# 03__Actuators_Driver_Sheet.net
KiCad netlist of a schematic drawn in Altium Designer
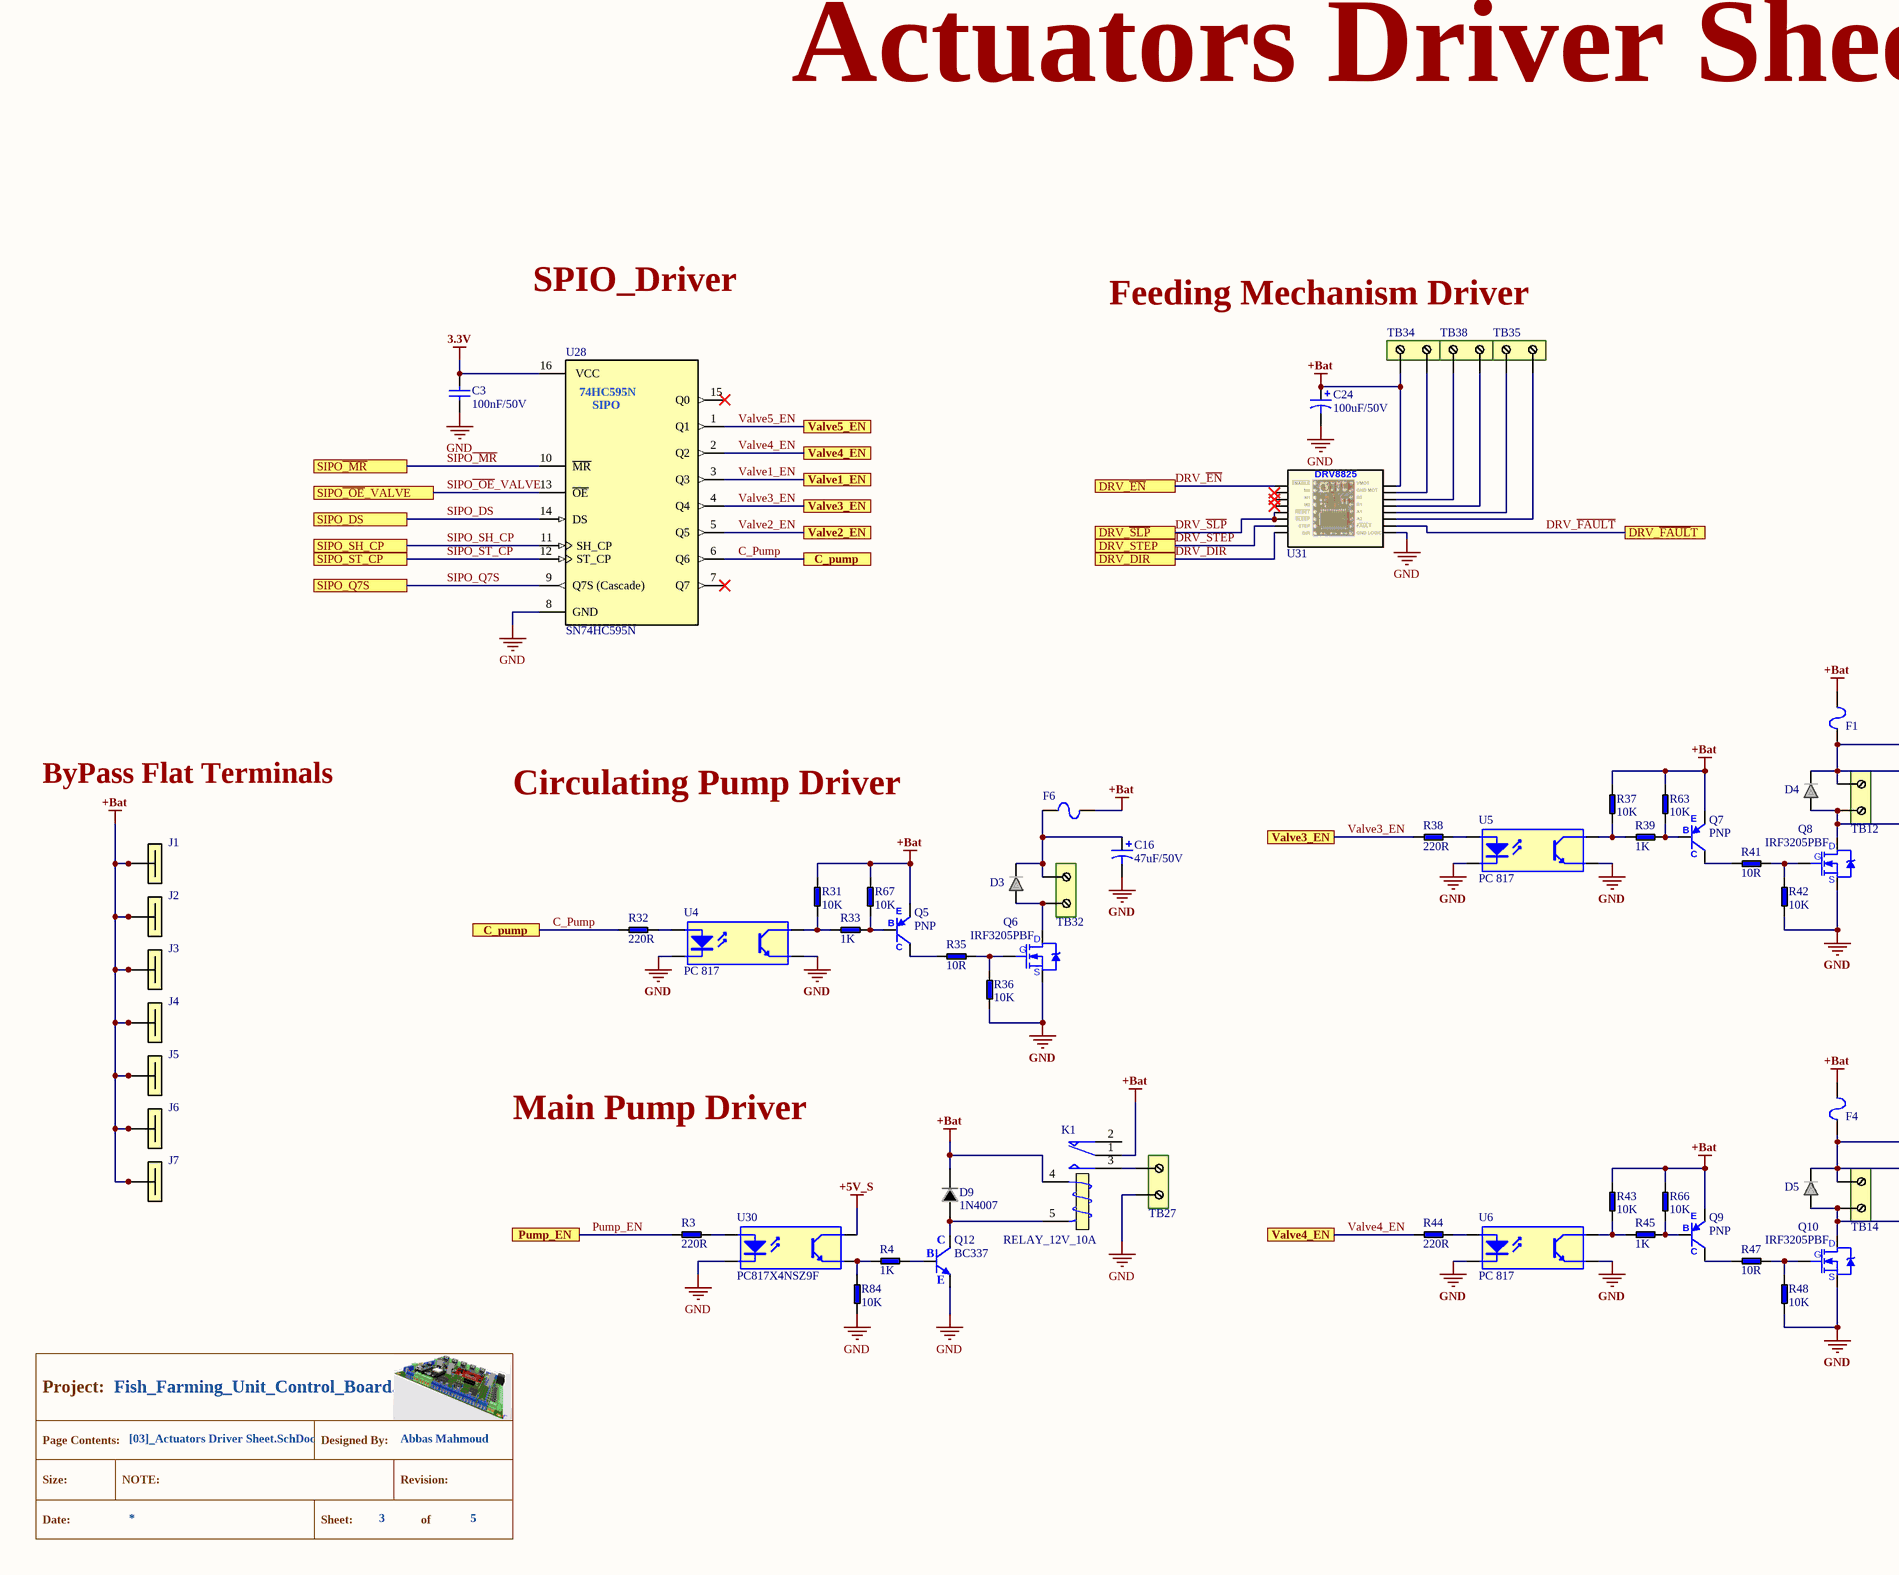
[diagram p0: [03]_Actuators Driver Sheet.SchDoc, left]
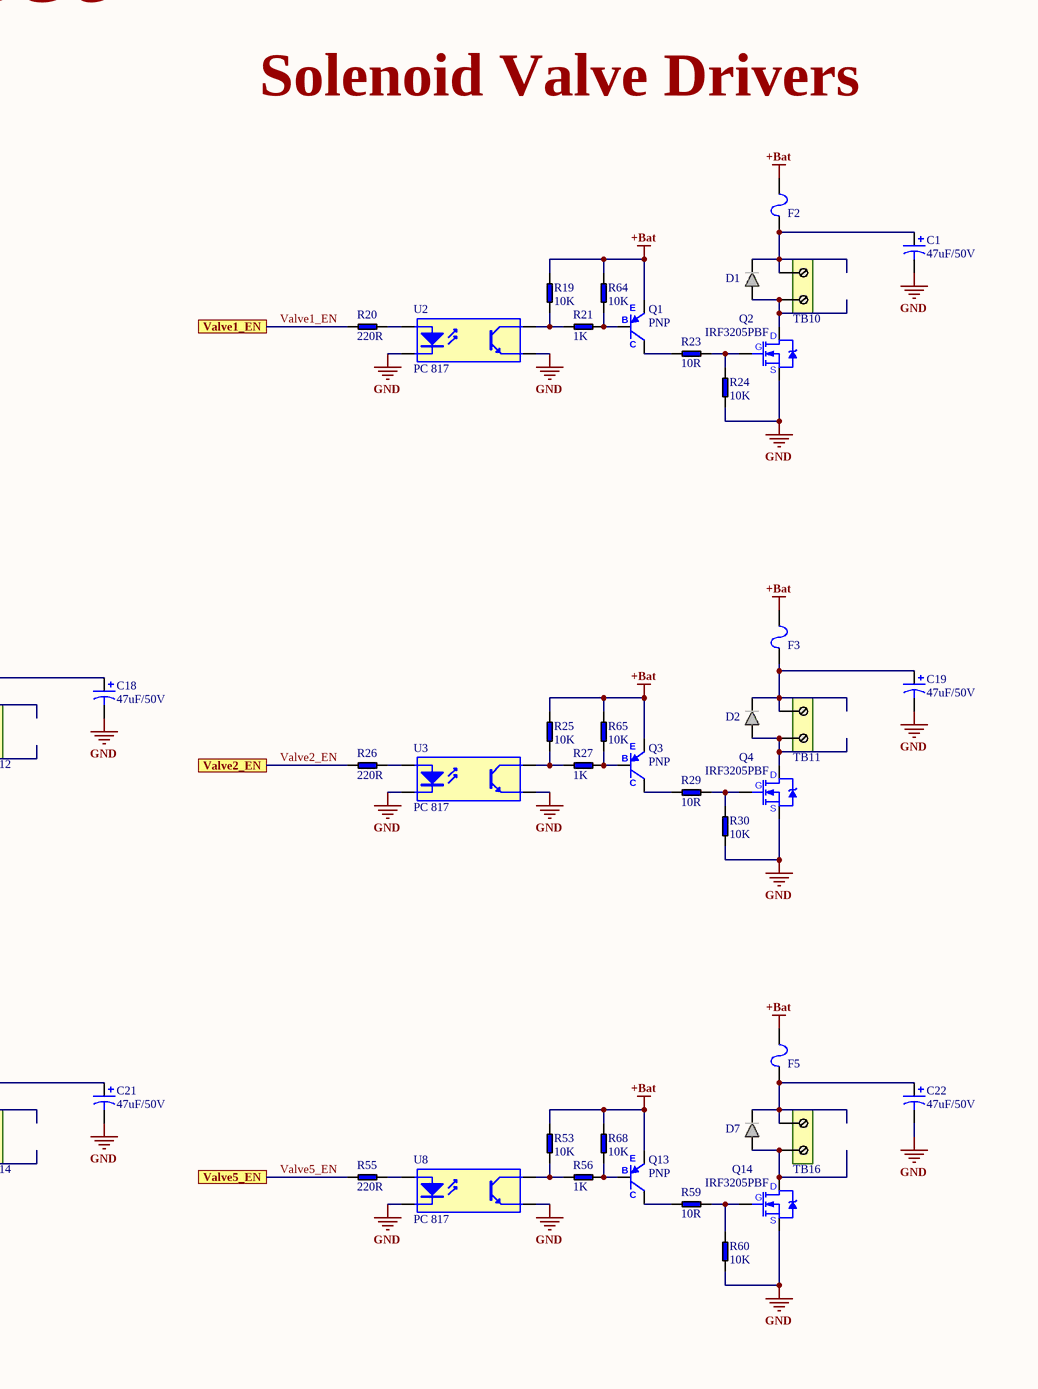
[diagram p1: [03]_Actuators Driver Sheet.SchDoc, right]

(export (version "E")
  (design (tool "Eeschema 10.0.6"))
  (components
    (comp (ref "C1")
      (value "47uF/50V")
      (footprint "ECAP - THT - 6.3X11X2.5MM")
      (description "47uF ±20% 50V 6.3x11 1000Hrs @ 105℃ Radial,6.3x11mm Aluminum Electrolytic Capacitors - Leaded RoHS")
      (libsource (lib "Altium_Abbas_V3") (part "ECAP - 47uF - 50V"))
    )
    (comp (ref "C3")
      (value "100nF/50V")
      (footprint "CCAP - PACKAGE - THT ,P = 2.54 MM")
      (description "100nF -20%~+80% 50V Through Hole,P=2.54mm Ceramic Disc Capacitors RoHS")
      (libsource (lib "Altium_Abbas_V3") (part "CCAP - 100nF - 50V - THT - P = 2.54"))
    )
    (comp (ref "C16")
      (value "47uF/50V")
      (footprint "ECAP - THT - 6.3X11X2.5MM")
      (description "47uF ±20% 50V 6.3x11 1000Hrs @ 105℃ Radial,6.3x11mm Aluminum Electrolytic Capacitors - Leaded RoHS")
      (libsource (lib "Altium_Abbas_V3") (part "ECAP - 47uF - 50V"))
    )
    (comp (ref "C18")
      (value "47uF/50V")
      (footprint "ECAP - THT - 6.3X11X2.5MM")
      (description "47uF ±20% 50V 6.3x11 1000Hrs @ 105℃ Radial,6.3x11mm Aluminum Electrolytic Capacitors - Leaded RoHS")
      (libsource (lib "Altium_Abbas_V3") (part "ECAP - 47uF - 50V"))
    )
    (comp (ref "C19")
      (value "47uF/50V")
      (footprint "ECAP - THT - 6.3X11X2.5MM")
      (description "47uF ±20% 50V 6.3x11 1000Hrs @ 105℃ Radial,6.3x11mm Aluminum Electrolytic Capacitors - Leaded RoHS")
      (libsource (lib "Altium_Abbas_V3") (part "ECAP - 47uF - 50V"))
    )
    (comp (ref "C21")
      (value "47uF/50V")
      (footprint "ECAP - THT - 6.3X11X2.5MM")
      (description "47uF ±20% 50V 6.3x11 1000Hrs @ 105℃ Radial,6.3x11mm Aluminum Electrolytic Capacitors - Leaded RoHS")
      (libsource (lib "Altium_Abbas_V3") (part "ECAP - 47uF - 50V"))
    )
    (comp (ref "C22")
      (value "47uF/50V")
      (footprint "ECAP - THT - 6.3X11X2.5MM")
      (description "47uF ±20% 50V 6.3x11 1000Hrs @ 105℃ Radial,6.3x11mm Aluminum Electrolytic Capacitors - Leaded RoHS")
      (libsource (lib "Altium_Abbas_V3") (part "ECAP - 47uF - 50V"))
    )
    (comp (ref "C24")
      (value "100uF/50V")
      (footprint "ECAP - THT - 8X12X3.5MM")
      (description "100uF ±20% 50V 8x12 1000Hrs @ 105℃ Radial,8x12mm Aluminum Electrolytic Capacitors - Leaded RoHS")
      (libsource (lib "Altium_Abbas_V3") (part "ECAP - 100uF - 50V"))
    )
    (comp (ref "D1")
      (value "DIODE")
      (footprint "DIODE-1n400X_0.3")
      (libsource (lib "Altium_Abbas") (part "DIODE"))
    )
    (comp (ref "D2")
      (value "DIODE")
      (footprint "DIODE-1n400X_0.3")
      (libsource (lib "Altium_Abbas") (part "DIODE"))
    )
    (comp (ref "D3")
      (value "DIODE")
      (footprint "DIODE-1n400X_0.3")
      (libsource (lib "Altium_Abbas") (part "DIODE"))
    )
    (comp (ref "D4")
      (value "DIODE")
      (footprint "DIODE-1n400X_0.3")
      (libsource (lib "Altium_Abbas") (part "DIODE"))
    )
    (comp (ref "D5")
      (value "DIODE")
      (footprint "DIODE-1n400X_0.3")
      (libsource (lib "Altium_Abbas") (part "DIODE"))
    )
    (comp (ref "D7")
      (value "DIODE")
      (footprint "DIODE-1n400X_0.3")
      (libsource (lib "Altium_Abbas") (part "DIODE"))
    )
    (comp (ref "D9")
      (value "1N4007")
      (footprint "DIODE - THT - 7.62P - PACKAGE - DO-41")
      (description "1kV 1A 1V @ 1A DO-41 Diodes - General Purpose RoHS")
      (libsource (lib "Altium_Abbas_V3") (part "Diode - 1N4007 - THT"))
    )
    (comp (ref "F1")
      (value "FUSES&HOLDERS")
      (footprint "FUSE-BLX-A HOLDER")
      (libsource (lib "Altium_Abbas_V3") (part "FUSES&HOLDERS"))
    )
    (comp (ref "F2")
      (value "FUSES&HOLDERS")
      (footprint "FUSE-BLX-A HOLDER")
      (libsource (lib "Altium_Abbas_V3") (part "FUSES&HOLDERS"))
    )
    (comp (ref "F3")
      (value "FUSES&HOLDERS")
      (footprint "FUSE-BLX-A HOLDER")
      (libsource (lib "Altium_Abbas_V3") (part "FUSES&HOLDERS"))
    )
    (comp (ref "F4")
      (value "FUSES&HOLDERS")
      (footprint "FUSE-BLX-A HOLDER")
      (libsource (lib "Altium_Abbas_V3") (part "FUSES&HOLDERS"))
    )
    (comp (ref "F5")
      (value "FUSES&HOLDERS")
      (footprint "FUSE-BLX-A HOLDER")
      (libsource (lib "Altium_Abbas_V3") (part "FUSES&HOLDERS"))
    )
    (comp (ref "F6")
      (value "FUSES&HOLDERS")
      (footprint "FUSE-BLX-A HOLDER")
      (libsource (lib "") (part "FUSES&HOLDERS_1"))
    )
    (comp (ref "J1")
      (value "1217861-1")
      (footprint "Terminal Male Flat 6.3mm")
      (description "Solder Tab Terminal; Uninsulated; Tin over Copper Plated; Straight; 6.35x0.83mm")
      (fields (field (name "MF") "TE Connectivity"))
      (libsource (lib "Altium_Abbas_V3") (part "Terminal Male Flat 6.3mm"))
    )
    (comp (ref "J2")
      (value "1217861-1")
      (footprint "Terminal Male Flat 6.3mm")
      (description "Solder Tab Terminal; Uninsulated; Tin over Copper Plated; Straight; 6.35x0.83mm")
      (fields (field (name "MF") "TE Connectivity"))
      (libsource (lib "Altium_Abbas_V3") (part "Terminal Male Flat 6.3mm"))
    )
    (comp (ref "J3")
      (value "1217861-1")
      (footprint "Terminal Male Flat 6.3mm")
      (description "Solder Tab Terminal; Uninsulated; Tin over Copper Plated; Straight; 6.35x0.83mm")
      (fields (field (name "MF") "TE Connectivity"))
      (libsource (lib "Altium_Abbas_V3") (part "Terminal Male Flat 6.3mm"))
    )
    (comp (ref "J4")
      (value "1217861-1")
      (footprint "Terminal Male Flat 6.3mm")
      (description "Solder Tab Terminal; Uninsulated; Tin over Copper Plated; Straight; 6.35x0.83mm")
      (fields (field (name "MF") "TE Connectivity"))
      (libsource (lib "Altium_Abbas_V3") (part "Terminal Male Flat 6.3mm"))
    )
    (comp (ref "J5")
      (value "1217861-1")
      (footprint "Terminal Male Flat 6.3mm")
      (description "Solder Tab Terminal; Uninsulated; Tin over Copper Plated; Straight; 6.35x0.83mm")
      (fields (field (name "MF") "TE Connectivity"))
      (libsource (lib "Altium_Abbas_V3") (part "Terminal Male Flat 6.3mm"))
    )
    (comp (ref "J6")
      (value "1217861-1")
      (footprint "Terminal Male Flat 6.3mm")
      (description "Solder Tab Terminal; Uninsulated; Tin over Copper Plated; Straight; 6.35x0.83mm")
      (fields (field (name "MF") "TE Connectivity"))
      (libsource (lib "Altium_Abbas_V3") (part "Terminal Male Flat 6.3mm"))
    )
    (comp (ref "J7")
      (value "1217861-1")
      (footprint "Terminal Male Flat 6.3mm")
      (description "Solder Tab Terminal; Uninsulated; Tin over Copper Plated; Straight; 6.35x0.83mm")
      (fields (field (name "MF") "TE Connectivity"))
      (libsource (lib "Altium_Abbas_V3") (part "Terminal Male Flat 6.3mm"))
    )
    (comp (ref "K1")
      (value "RELAY_12V_10A")
      (footprint "RELAY - THT - 10A")
      (description "SPDT Relay")
      (fields (field (name "PUBLISHER") "Altium Limited"))
      (libsource (lib "Altium_Abbas_V3") (part "Relay_12V_10A"))
    )
    (comp (ref "Q1")
      (value "PNP")
      (footprint "Transistor-TO-92A")
      (libsource (lib "Altium_Abbas") (part "PNP"))
    )
    (comp (ref "Q2")
      (value "IRF3205PBF")
      (footprint "Transistor/Heatsink -TO-220")
      (description "N Channel 55V 110A 4V @ 250uA 8mΩ @ 62A,10V 200W TO-220(TO-220-3) MOSFET RoHS")
      (fields (field (name "MF") "Infineon Technologies") (field (name "MP") "IRF3205SPBF"))
      (libsource (lib "Altium_Abbas") (part "IRF3205PBF"))
    )
    (comp (ref "Q3")
      (value "PNP")
      (footprint "Transistor-TO-92A")
      (libsource (lib "Altium_Abbas") (part "PNP"))
    )
    (comp (ref "Q4")
      (value "IRF3205PBF")
      (footprint "Transistor/Heatsink -TO-220")
      (description "N Channel 55V 110A 4V @ 250uA 8mΩ @ 62A,10V 200W TO-220(TO-220-3) MOSFET RoHS")
      (fields (field (name "MF") "Infineon Technologies") (field (name "MP") "IRF3205SPBF"))
      (libsource (lib "Altium_Abbas") (part "IRF3205PBF"))
    )
    (comp (ref "Q5")
      (value "PNP")
      (footprint "Transistor-TO-92A")
      (libsource (lib "Altium_Abbas") (part "PNP"))
    )
    (comp (ref "Q6")
      (value "IRF3205PBF")
      (footprint "Transistor/Heatsink -TO-220")
      (description "N Channel 55V 110A 4V @ 250uA 8mΩ @ 62A,10V 200W TO-220(TO-220-3) MOSFET RoHS")
      (fields (field (name "MF") "Infineon Technologies") (field (name "MP") "IRF3205SPBF"))
      (libsource (lib "Altium_Abbas") (part "IRF3205PBF"))
    )
    (comp (ref "Q7")
      (value "PNP")
      (footprint "Transistor-TO-92A")
      (libsource (lib "Altium_Abbas") (part "PNP"))
    )
    (comp (ref "Q8")
      (value "IRF3205PBF")
      (footprint "Transistor/Heatsink -TO-220")
      (description "N Channel 55V 110A 4V @ 250uA 8mΩ @ 62A,10V 200W TO-220(TO-220-3) MOSFET RoHS")
      (fields (field (name "MF") "Infineon Technologies") (field (name "MP") "IRF3205SPBF"))
      (libsource (lib "Altium_Abbas") (part "IRF3205PBF"))
    )
    (comp (ref "Q9")
      (value "PNP")
      (footprint "Transistor-TO-92A")
      (libsource (lib "Altium_Abbas") (part "PNP"))
    )
    (comp (ref "Q10")
      (value "IRF3205PBF")
      (footprint "Transistor/Heatsink -TO-220")
      (description "N Channel 55V 110A 4V @ 250uA 8mΩ @ 62A,10V 200W TO-220(TO-220-3) MOSFET RoHS")
      (fields (field (name "MF") "Infineon Technologies") (field (name "MP") "IRF3205SPBF"))
      (libsource (lib "Altium_Abbas") (part "IRF3205PBF"))
    )
    (comp (ref "Q12")
      (value "BC337")
      (footprint "Transistor - THT - PACKAGE - TO-92 / TO-92-3")
      (description "NPN 800mA 45V 625mW TO-92(TO-92-3) Transistors (NPN/PNP) RoHS")
      (libsource (lib "Altium_Abbas_V3") (part "NPN - BC337"))
    )
    (comp (ref "Q13")
      (value "PNP")
      (footprint "Transistor-TO-92A")
      (libsource (lib "Altium_Abbas") (part "PNP"))
    )
    (comp (ref "Q14")
      (value "IRF3205PBF")
      (footprint "Transistor/Heatsink -TO-220")
      (description "N Channel 55V 110A 4V @ 250uA 8mΩ @ 62A,10V 200W TO-220(TO-220-3) MOSFET RoHS")
      (fields (field (name "MF") "Infineon Technologies") (field (name "MP") "IRF3205SPBF"))
      (libsource (lib "Altium_Abbas") (part "IRF3205PBF"))
    )
    (comp (ref "R3")
      (value "220R")
      (footprint "R - THT - P5.0 - 1/4W")
      (description "220R ±1% 1/4W ±100ppm/℃ Axial Metal Film Resistor_ Throuh Hole Technology RoHS")
      (libsource (lib "Altium_Abbas_V3") (part "R220R - THT"))
    )
    (comp (ref "R4")
      (value "1K")
      (footprint "R - THT - P5.0 - 1/4W")
      (description "1K ±1% 1/4W ±100ppm/℃ Axial Metal Film Resistor_ Throuh Hole Technology RoHS")
      (libsource (lib "Altium_Abbas_V3") (part "R1K - THT"))
    )
    (comp (ref "R19")
      (value "10K")
      (footprint "R-THT_5.08mm-1/4W")
      (description "10K ±1% 1/4W ±100ppm/℃ Axial Metal Film Resistor_ Throuh Hole Technology RoHS")
      (libsource (lib "Altium_Abbas") (part "R10K-THT"))
    )
    (comp (ref "R20")
      (value "220R")
      (footprint "R-THT_5.08mm-1/4W")
      (description "220R ±1% 1/4W ±100ppm/℃ Axial Metal Film Resistor_ Throuh Hole Technology RoHS")
      (libsource (lib "Altium_Abbas") (part "R220R-THT"))
    )
    (comp (ref "R21")
      (value "1K")
      (footprint "R-THT_5.08mm-1/4W")
      (description "1K ±1% 1/4W ±100ppm/℃ Axial Metal Film Resistor_ Throuh Hole Technology RoHS")
      (libsource (lib "Altium_Abbas") (part "R1K-THT"))
    )
    (comp (ref "R23")
      (value "10R")
      (footprint "R-THT_5.08mm-1/4W")
      (description "10R ±1% 1/4W ±100ppm/℃ Axial Metal Film Resistor_ Throuh Hole Technology RoHS")
      (libsource (lib "Altium_Abbas") (part "R10R-THT"))
    )
    (comp (ref "R24")
      (value "10K")
      (footprint "R-THT_5.08mm-1/4W")
      (description "10K ±1% 1/4W ±100ppm/℃ Axial Metal Film Resistor_ Throuh Hole Technology RoHS")
      (libsource (lib "Altium_Abbas") (part "R10K-THT"))
    )
    (comp (ref "R25")
      (value "10K")
      (footprint "R-THT_5.08mm-1/4W")
      (description "10K ±1% 1/4W ±100ppm/℃ Axial Metal Film Resistor_ Throuh Hole Technology RoHS")
      (libsource (lib "Altium_Abbas") (part "R10K-THT"))
    )
    (comp (ref "R26")
      (value "220R")
      (footprint "R-THT_5.08mm-1/4W")
      (description "220R ±1% 1/4W ±100ppm/℃ Axial Metal Film Resistor_ Throuh Hole Technology RoHS")
      (libsource (lib "Altium_Abbas") (part "R220R-THT"))
    )
    (comp (ref "R27")
      (value "1K")
      (footprint "R-THT_5.08mm-1/4W")
      (description "1K ±1% 1/4W ±100ppm/℃ Axial Metal Film Resistor_ Throuh Hole Technology RoHS")
      (libsource (lib "Altium_Abbas") (part "R1K-THT"))
    )
    (comp (ref "R29")
      (value "10R")
      (footprint "R-THT_5.08mm-1/4W")
      (description "10R ±1% 1/4W ±100ppm/℃ Axial Metal Film Resistor_ Throuh Hole Technology RoHS")
      (libsource (lib "Altium_Abbas") (part "R10R-THT"))
    )
    (comp (ref "R30")
      (value "10K")
      (footprint "R-THT_5.08mm-1/4W")
      (description "10K ±1% 1/4W ±100ppm/℃ Axial Metal Film Resistor_ Throuh Hole Technology RoHS")
      (libsource (lib "Altium_Abbas") (part "R10K-THT"))
    )
    (comp (ref "R31")
      (value "10K")
      (footprint "R-THT_5.08mm-1/4W")
      (description "10K ±1% 1/4W ±100ppm/℃ Axial Metal Film Resistor_ Throuh Hole Technology RoHS")
      (libsource (lib "Altium_Abbas") (part "R10K-THT"))
    )
    (comp (ref "R32")
      (value "220R")
      (footprint "R-THT_5.08mm-1/4W")
      (description "220R ±1% 1/4W ±100ppm/℃ Axial Metal Film Resistor_ Throuh Hole Technology RoHS")
      (libsource (lib "Altium_Abbas") (part "R220R-THT"))
    )
    (comp (ref "R33")
      (value "1K")
      (footprint "R-THT_5.08mm-1/4W")
      (description "1K ±1% 1/4W ±100ppm/℃ Axial Metal Film Resistor_ Throuh Hole Technology RoHS")
      (libsource (lib "Altium_Abbas") (part "R1K-THT"))
    )
    (comp (ref "R35")
      (value "10R")
      (footprint "R-THT_5.08mm-1/4W")
      (description "10R ±1% 1/4W ±100ppm/℃ Axial Metal Film Resistor_ Throuh Hole Technology RoHS")
      (libsource (lib "Altium_Abbas") (part "R10R-THT"))
    )
    (comp (ref "R36")
      (value "10K")
      (footprint "R-THT_5.08mm-1/4W")
      (description "10K ±1% 1/4W ±100ppm/℃ Axial Metal Film Resistor_ Throuh Hole Technology RoHS")
      (libsource (lib "Altium_Abbas") (part "R10K-THT"))
    )
    (comp (ref "R37")
      (value "10K")
      (footprint "R-THT_5.08mm-1/4W")
      (description "10K ±1% 1/4W ±100ppm/℃ Axial Metal Film Resistor_ Throuh Hole Technology RoHS")
      (libsource (lib "Altium_Abbas") (part "R10K-THT"))
    )
    (comp (ref "R38")
      (value "220R")
      (footprint "R-THT_5.08mm-1/4W")
      (description "220R ±1% 1/4W ±100ppm/℃ Axial Metal Film Resistor_ Throuh Hole Technology RoHS")
      (libsource (lib "Altium_Abbas") (part "R220R-THT"))
    )
    (comp (ref "R39")
      (value "1K")
      (footprint "R-THT_5.08mm-1/4W")
      (description "1K ±1% 1/4W ±100ppm/℃ Axial Metal Film Resistor_ Throuh Hole Technology RoHS")
      (libsource (lib "Altium_Abbas") (part "R1K-THT"))
    )
    (comp (ref "R41")
      (value "10R")
      (footprint "R-THT_5.08mm-1/4W")
      (description "10R ±1% 1/4W ±100ppm/℃ Axial Metal Film Resistor_ Throuh Hole Technology RoHS")
      (libsource (lib "Altium_Abbas") (part "R10R-THT"))
    )
    (comp (ref "R42")
      (value "10K")
      (footprint "R-THT_5.08mm-1/4W")
      (description "10K ±1% 1/4W ±100ppm/℃ Axial Metal Film Resistor_ Throuh Hole Technology RoHS")
      (libsource (lib "Altium_Abbas") (part "R10K-THT"))
    )
    (comp (ref "R43")
      (value "10K")
      (footprint "R-THT_5.08mm-1/4W")
      (description "10K ±1% 1/4W ±100ppm/℃ Axial Metal Film Resistor_ Throuh Hole Technology RoHS")
      (libsource (lib "Altium_Abbas") (part "R10K-THT"))
    )
    (comp (ref "R44")
      (value "220R")
      (footprint "R-THT_5.08mm-1/4W")
      (description "220R ±1% 1/4W ±100ppm/℃ Axial Metal Film Resistor_ Throuh Hole Technology RoHS")
      (libsource (lib "Altium_Abbas") (part "R220R-THT"))
    )
    (comp (ref "R45")
      (value "1K")
      (footprint "R-THT_5.08mm-1/4W")
      (description "1K ±1% 1/4W ±100ppm/℃ Axial Metal Film Resistor_ Throuh Hole Technology RoHS")
      (libsource (lib "Altium_Abbas") (part "R1K-THT"))
    )
    (comp (ref "R47")
      (value "10R")
      (footprint "R-THT_5.08mm-1/4W")
      (description "10R ±1% 1/4W ±100ppm/℃ Axial Metal Film Resistor_ Throuh Hole Technology RoHS")
      (libsource (lib "Altium_Abbas") (part "R10R-THT"))
    )
    (comp (ref "R48")
      (value "10K")
      (footprint "R-THT_5.08mm-1/4W")
      (description "10K ±1% 1/4W ±100ppm/℃ Axial Metal Film Resistor_ Throuh Hole Technology RoHS")
      (libsource (lib "Altium_Abbas") (part "R10K-THT"))
    )
    (comp (ref "R53")
      (value "10K")
      (footprint "R-THT_5.08mm-1/4W")
      (description "10K ±1% 1/4W ±100ppm/℃ Axial Metal Film Resistor_ Throuh Hole Technology RoHS")
      (libsource (lib "Altium_Abbas") (part "R10K-THT"))
    )
    (comp (ref "R55")
      (value "220R")
      (footprint "R-THT_5.08mm-1/4W")
      (description "220R ±1% 1/4W ±100ppm/℃ Axial Metal Film Resistor_ Throuh Hole Technology RoHS")
      (libsource (lib "Altium_Abbas") (part "R220R-THT"))
    )
    (comp (ref "R56")
      (value "1K")
      (footprint "R-THT_5.08mm-1/4W")
      (description "1K ±1% 1/4W ±100ppm/℃ Axial Metal Film Resistor_ Throuh Hole Technology RoHS")
      (libsource (lib "Altium_Abbas") (part "R1K-THT"))
    )
    (comp (ref "R59")
      (value "10R")
      (footprint "R-THT_5.08mm-1/4W")
      (description "10R ±1% 1/4W ±100ppm/℃ Axial Metal Film Resistor_ Throuh Hole Technology RoHS")
      (libsource (lib "Altium_Abbas") (part "R10R-THT"))
    )
    (comp (ref "R60")
      (value "10K")
      (footprint "R-THT_5.08mm-1/4W")
      (description "10K ±1% 1/4W ±100ppm/℃ Axial Metal Film Resistor_ Throuh Hole Technology RoHS")
      (libsource (lib "Altium_Abbas") (part "R10K-THT"))
    )
    (comp (ref "R63")
      (value "10K")
      (footprint "R-THT_5.08mm-1/4W")
      (description "10K ±1% 1/4W ±100ppm/℃ Axial Metal Film Resistor_ Throuh Hole Technology RoHS")
      (libsource (lib "Altium_Abbas") (part "R10K-THT"))
    )
    (comp (ref "R64")
      (value "10K")
      (footprint "R-THT_5.08mm-1/4W")
      (description "10K ±1% 1/4W ±100ppm/℃ Axial Metal Film Resistor_ Throuh Hole Technology RoHS")
      (libsource (lib "Altium_Abbas") (part "R10K-THT"))
    )
    (comp (ref "R65")
      (value "10K")
      (footprint "R-THT_5.08mm-1/4W")
      (description "10K ±1% 1/4W ±100ppm/℃ Axial Metal Film Resistor_ Throuh Hole Technology RoHS")
      (libsource (lib "Altium_Abbas") (part "R10K-THT"))
    )
    (comp (ref "R66")
      (value "10K")
      (footprint "R-THT_5.08mm-1/4W")
      (description "10K ±1% 1/4W ±100ppm/℃ Axial Metal Film Resistor_ Throuh Hole Technology RoHS")
      (libsource (lib "Altium_Abbas") (part "R10K-THT"))
    )
    (comp (ref "R67")
      (value "10K")
      (footprint "R-THT_5.08mm-1/4W")
      (description "10K ±1% 1/4W ±100ppm/℃ Axial Metal Film Resistor_ Throuh Hole Technology RoHS")
      (libsource (lib "Altium_Abbas") (part "R10K-THT"))
    )
    (comp (ref "R68")
      (value "10K")
      (footprint "R-THT_5.08mm-1/4W")
      (description "10K ±1% 1/4W ±100ppm/℃ Axial Metal Film Resistor_ Throuh Hole Technology RoHS")
      (libsource (lib "Altium_Abbas") (part "R10K-THT"))
    )
    (comp (ref "R84")
      (value "10K")
      (footprint "R - THT - P5.0 - 1/4W")
      (description "10K ±1% 1/4W ±100ppm/℃ Axial Metal Film Resistor_ Throuh Hole Technology RoHS")
      (libsource (lib "Altium_Abbas_V3") (part "R10K - THT"))
    )
    (comp (ref "TB10")
      (value "2 Pins Pluggable")
      (footprint "TERMINAL BLOCK - 2 PINS - PACKAGE - PLUGGABLE - THT - P = 5.08MM - Horizontal _ Plug+Receptable")
      (libsource (lib "Altium_Abbas_V3") (part "Terminal Block - 2 Pins - Pluggable"))
    )
    (comp (ref "TB11")
      (value "2 Pins Pluggable")
      (footprint "TERMINAL BLOCK - 2 PINS - PACKAGE - PLUGGABLE - THT - P = 5.08MM - Horizontal _ Plug+Receptable")
      (libsource (lib "Altium_Abbas_V3") (part "Terminal Block - 2 Pins - Pluggable"))
    )
    (comp (ref "TB12")
      (value "2 Pins Pluggable")
      (footprint "TERMINAL BLOCK - 2 PINS - PACKAGE - PLUGGABLE - THT - P = 5.08MM - Horizontal _ Plug+Receptable")
      (libsource (lib "Altium_Abbas_V3") (part "Terminal Block - 2 Pins - Pluggable"))
    )
    (comp (ref "TB14")
      (value "2 Pins Pluggable")
      (footprint "TERMINAL BLOCK - 2 PINS - PACKAGE - PLUGGABLE - THT - P = 5.08MM - Horizontal _ Plug+Receptable")
      (libsource (lib "Altium_Abbas_V3") (part "Terminal Block - 2 Pins - Pluggable"))
    )
    (comp (ref "TB16")
      (value "2 Pins Pluggable")
      (footprint "TERMINAL BLOCK - 2 PINS - PACKAGE - PLUGGABLE - THT - P = 5.08MM - Horizontal _ Plug+Receptable")
      (libsource (lib "Altium_Abbas_V3") (part "Terminal Block - 2 Pins - Pluggable"))
    )
    (comp (ref "TB27")
      (value "2 Pins Pluggable")
      (footprint "TERMINAL BLOCK - 2 PINS - PACKAGE - PLUGGABLE - THT - P = 5.08MM - Horizontal _ Plug+Receptable")
      (libsource (lib "") (part "Terminal Block - 2 Pins - Pluggable_1"))
    )
    (comp (ref "TB32")
      (value "2 Pins Pluggable")
      (footprint "TERMINAL BLOCK - 2 PINS - PACKAGE - PLUGGABLE - THT - P = 5.08MM - Horizontal _ Plug+Receptable")
      (libsource (lib "") (part "Terminal Block - 2 Pins - Pluggable_1"))
    )
    (comp (ref "TB34")
      (value "2 Pins Pluggable")
      (footprint "TERMINAL BLOCK - 2 PINS - PACKAGE - PLUGGABLE - THT - P = 5.08MM - Horizontal _ Plug+Receptable")
      (libsource (lib "") (part "Terminal Block - 2 Pins - Pluggable_1"))
    )
    (comp (ref "TB35")
      (value "2 Pins Pluggable")
      (footprint "TERMINAL BLOCK - 2 PINS - PACKAGE - PLUGGABLE - THT - P = 5.08MM - Horizontal _ Plug+Receptable")
      (libsource (lib "") (part "Terminal Block - 2 Pins - Pluggable_1"))
    )
    (comp (ref "TB38")
      (value "2 Pins Pluggable")
      (footprint "TERMINAL BLOCK - 2 PINS - PACKAGE - PLUGGABLE - THT - P = 5.08MM - Horizontal _ Plug+Receptable")
      (libsource (lib "") (part "Terminal Block - 2 Pins - Pluggable_1"))
    )
    (comp (ref "U2")
      (value "PC 817")
      (footprint "IC_DIP4")
      (description "4-Pin Phototransistor Optocoupler")
      (fields (field (name "PUBLISHER") "Altium Limited"))
      (libsource (lib "Altium_Abbas") (part "PC 817"))
    )
    (comp (ref "U3")
      (value "PC 817")
      (footprint "IC_DIP4")
      (description "4-Pin Phototransistor Optocoupler")
      (fields (field (name "PUBLISHER") "Altium Limited"))
      (libsource (lib "Altium_Abbas") (part "PC 817"))
    )
    (comp (ref "U4")
      (value "PC 817")
      (footprint "IC_DIP4")
      (description "4-Pin Phototransistor Optocoupler")
      (fields (field (name "PUBLISHER") "Altium Limited"))
      (libsource (lib "Altium_Abbas") (part "PC 817"))
    )
    (comp (ref "U5")
      (value "PC 817")
      (footprint "IC_DIP4")
      (description "4-Pin Phototransistor Optocoupler")
      (fields (field (name "PUBLISHER") "Altium Limited"))
      (libsource (lib "Altium_Abbas") (part "PC 817"))
    )
    (comp (ref "U6")
      (value "PC 817")
      (footprint "IC_DIP4")
      (description "4-Pin Phototransistor Optocoupler")
      (fields (field (name "PUBLISHER") "Altium Limited"))
      (libsource (lib "Altium_Abbas") (part "PC 817"))
    )
    (comp (ref "U8")
      (value "PC 817")
      (footprint "IC_DIP4")
      (description "4-Pin Phototransistor Optocoupler")
      (fields (field (name "PUBLISHER") "Altium Limited"))
      (libsource (lib "Altium_Abbas") (part "PC 817"))
    )
    (comp (ref "U28")
      (value "SN74HC595N")
      (footprint "ICB - DIP-16")
      (description "Serial to Parallel or Serial Shift Register Supplementary type DIP-16 Shift Registers RoHS")
      (fields (field (name "MANUFACTURER") "Texas Instruments"))
      (libsource (lib "Altium_Abbas_V3") (part "IC - SN74HC595N"))
    )
    (comp (ref "U30")
      (value "PC817X4NSZ9F")
      (footprint "ICB - DIP-4")
      (description "Optoisolator Transistor Output 5000Vrms 1 Channel 4-DIP")
      (fields (field (name "MANUFACTURER") "Sharp Microelectronics"))
      (libsource (lib "Altium_Abbas_V3") (part "IC - PC817X4NSZ9F"))
    )
    (comp (ref "U31")
      (value "DRV8825")
      (footprint "drv8825")
      (description "MEGAPI STEPPER MOTOR DRIVER")
      (libsource (lib "Altium_Modules") (part "DRV8825"))
    )
  )
  (nets
    (net (code "1") (name "+5V_S") (class "Default")
      (node (ref "U30") (pin "4") (pinfunction "C_4") (pintype "passive"))
    )
    (net (code "2") (name "+Bat") (class "Default")
      (node (ref "C24") (pin "A") (pinfunction "A_A") (pintype "passive"))
      (node (ref "D9") (pin "K") (pinfunction "K_K") (pintype "passive"))
      (node (ref "F1") (pin "1") (pintype "passive"))
      (node (ref "F2") (pin "1") (pintype "passive"))
      (node (ref "F3") (pin "1") (pintype "passive"))
      (node (ref "F4") (pin "1") (pintype "passive"))
      (node (ref "F5") (pin "1") (pintype "passive"))
      (node (ref "F6") (pin "2") (pintype "passive"))
      (node (ref "J1") (pin "1") (pinfunction "1_1") (pintype "passive"))
      (node (ref "J1") (pin "2") (pinfunction "1_2") (pintype "passive"))
      (node (ref "J2") (pin "1") (pinfunction "1_1") (pintype "passive"))
      (node (ref "J2") (pin "2") (pinfunction "1_2") (pintype "passive"))
      (node (ref "J3") (pin "1") (pinfunction "1_1") (pintype "passive"))
      (node (ref "J3") (pin "2") (pinfunction "1_2") (pintype "passive"))
      (node (ref "J4") (pin "1") (pinfunction "1_1") (pintype "passive"))
      (node (ref "J4") (pin "2") (pinfunction "1_2") (pintype "passive"))
      (node (ref "J5") (pin "1") (pinfunction "1_1") (pintype "passive"))
      (node (ref "J5") (pin "2") (pinfunction "1_2") (pintype "passive"))
      (node (ref "J6") (pin "1") (pinfunction "1_1") (pintype "passive"))
      (node (ref "J6") (pin "2") (pinfunction "1_2") (pintype "passive"))
      (node (ref "J7") (pin "1") (pinfunction "1_1") (pintype "passive"))
      (node (ref "J7") (pin "2") (pinfunction "1_2") (pintype "passive"))
      (node (ref "K1") (pin "1") (pinfunction "COM_1") (pintype "passive"))
      (node (ref "K1") (pin "4") (pinfunction "T1_4") (pintype "passive"))
      (node (ref "Q1") (pin "1") (pinfunction "E_1") (pintype "passive"))
      (node (ref "Q13") (pin "1") (pinfunction "E_1") (pintype "passive"))
      (node (ref "Q3") (pin "1") (pinfunction "E_1") (pintype "passive"))
      (node (ref "Q5") (pin "1") (pinfunction "E_1") (pintype "passive"))
      (node (ref "Q7") (pin "1") (pinfunction "E_1") (pintype "passive"))
      (node (ref "Q9") (pin "1") (pinfunction "E_1") (pintype "passive"))
      (node (ref "R19") (pin "2") (pinfunction "6_2") (pintype "passive"))
      (node (ref "R25") (pin "2") (pinfunction "6_2") (pintype "passive"))
      (node (ref "R31") (pin "2") (pinfunction "6_2") (pintype "passive"))
      (node (ref "R37") (pin "2") (pinfunction "6_2") (pintype "passive"))
      (node (ref "R43") (pin "2") (pinfunction "6_2") (pintype "passive"))
      (node (ref "R53") (pin "2") (pinfunction "6_2") (pintype "passive"))
      (node (ref "R63") (pin "2") (pinfunction "6_2") (pintype "passive"))
      (node (ref "R64") (pin "2") (pinfunction "6_2") (pintype "passive"))
      (node (ref "R65") (pin "2") (pinfunction "6_2") (pintype "passive"))
      (node (ref "R66") (pin "2") (pinfunction "6_2") (pintype "passive"))
      (node (ref "R67") (pin "2") (pinfunction "6_2") (pintype "passive"))
      (node (ref "R68") (pin "2") (pinfunction "6_2") (pintype "passive"))
      (node (ref "TB34") (pin "2") (pinfunction "2_2") (pintype "passive"))
      (node (ref "U31") (pin "V_MOT") (pinfunction "V_MOT_V_MOT") (pintype "passive"))
    )
    (net (code "3") (name "/C_Pump") (class "Default")
      (node (ref "R32") (pin "1") (pinfunction "5_1") (pintype "passive"))
      (node (ref "U28") (pin "6") (pinfunction "Q6_6") (pintype "output"))
    )
    (net (code "4") (name "/DRV_DIR") (class "Default")
      (node (ref "U31") (pin "DIR") (pinfunction "DIR_DIR") (pintype "passive"))
    )
    (net (code "5") (name "/DRV_STEP") (class "Default")
      (node (ref "U31") (pin "STEP") (pinfunction "STEP_STEP") (pintype "passive"))
    )
    (net (code "6") (name "/DRV_~{EN}") (class "Default")
      (node (ref "U31") (pin "ENABLE") (pinfunction "ENABLE_ENABLE") (pintype "passive"))
    )
    (net (code "7") (name "/DRV_~{FAULT}") (class "Default")
      (node (ref "U31") (pin "FAULT") (pinfunction "FAULT_FAULT") (pintype "passive"))
    )
    (net (code "8") (name "/DRV_~{SLP}") (class "Default")
      (node (ref "U31") (pin "RESET") (pinfunction "RESET_RESET") (pintype "passive"))
      (node (ref "U31") (pin "SLEEP") (pinfunction "SLEEP_SLEEP") (pintype "passive"))
    )
    (net (code "9") (name "/Pump_EN") (class "Default")
      (node (ref "R3") (pin "1") (pinfunction "5_1") (pintype "passive"))
    )
    (net (code "10") (name "/SIPO_DS") (class "Default")
      (node (ref "U28") (pin "14") (pinfunction "DS_14") (pintype "input"))
    )
    (net (code "11") (name "/SIPO_Q7S") (class "Default")
      (node (ref "U28") (pin "9") (pinfunction "Q7S_(Cascade)_9") (pintype "output"))
    )
    (net (code "12") (name "/SIPO_SH_CP") (class "Default")
      (node (ref "U28") (pin "11") (pinfunction "SH_CP_11") (pintype "input"))
    )
    (net (code "13") (name "/SIPO_ST_CP") (class "Default")
      (node (ref "U28") (pin "12") (pinfunction "ST_CP_12") (pintype "input"))
    )
    (net (code "14") (name "/SIPO~{_MR}") (class "Default")
      (node (ref "U28") (pin "10") (pinfunction "~{MR}_10") (pintype "passive"))
    )
    (net (code "15") (name "/SIPO~{_OE}_VALVE") (class "Default")
      (node (ref "U28") (pin "13") (pinfunction "~{OE}_13") (pintype "passive"))
    )
    (net (code "16") (name "/Valve1_EN") (class "Default")
      (node (ref "R20") (pin "1") (pinfunction "5_1") (pintype "passive"))
      (node (ref "U28") (pin "3") (pinfunction "Q3_3") (pintype "output"))
    )
    (net (code "17") (name "/Valve2_EN") (class "Default")
      (node (ref "R26") (pin "1") (pinfunction "5_1") (pintype "passive"))
      (node (ref "U28") (pin "5") (pinfunction "Q5_5") (pintype "output"))
    )
    (net (code "18") (name "/Valve3_EN") (class "Default")
      (node (ref "R38") (pin "1") (pinfunction "5_1") (pintype "passive"))
      (node (ref "U28") (pin "4") (pinfunction "Q4_4") (pintype "output"))
    )
    (net (code "19") (name "/Valve4_EN") (class "Default")
      (node (ref "R44") (pin "1") (pinfunction "5_1") (pintype "passive"))
      (node (ref "U28") (pin "2") (pinfunction "Q2_2") (pintype "output"))
    )
    (net (code "20") (name "/Valve5_EN") (class "Default")
      (node (ref "R55") (pin "1") (pinfunction "5_1") (pintype "passive"))
      (node (ref "U28") (pin "1") (pinfunction "Q1_1") (pintype "output"))
    )
    (net (code "21") (name "3.3V") (class "Default")
      (node (ref "C3") (pin "1") (pinfunction "1_1") (pintype "passive"))
      (node (ref "U28") (pin "16") (pinfunction "VCC_16") (pintype "passive"))
    )
    (net (code "22") (name "GND") (class "Default")
      (node (ref "C1") (pin "K") (pinfunction "K_K") (pintype "passive"))
      (node (ref "C16") (pin "K") (pinfunction "K_K") (pintype "passive"))
      (node (ref "C18") (pin "K") (pinfunction "K_K") (pintype "passive"))
      (node (ref "C19") (pin "K") (pinfunction "K_K") (pintype "passive"))
      (node (ref "C21") (pin "K") (pinfunction "K_K") (pintype "passive"))
      (node (ref "C22") (pin "K") (pinfunction "K_K") (pintype "passive"))
      (node (ref "C24") (pin "K") (pinfunction "K_K") (pintype "passive"))
      (node (ref "C3") (pin "2") (pinfunction "2_2") (pintype "passive"))
      (node (ref "Q10") (pin "3") (pinfunction "S_3") (pintype "passive"))
      (node (ref "Q12") (pin "1") (pinfunction "E_1") (pintype "passive"))
      (node (ref "Q14") (pin "3") (pinfunction "S_3") (pintype "passive"))
      (node (ref "Q2") (pin "3") (pinfunction "S_3") (pintype "passive"))
      (node (ref "Q4") (pin "3") (pinfunction "S_3") (pintype "passive"))
      (node (ref "Q6") (pin "3") (pinfunction "S_3") (pintype "passive"))
      (node (ref "Q8") (pin "3") (pinfunction "S_3") (pintype "passive"))
      (node (ref "R24") (pin "1") (pinfunction "5_1") (pintype "passive"))
      (node (ref "R30") (pin "1") (pinfunction "5_1") (pintype "passive"))
      (node (ref "R36") (pin "1") (pinfunction "5_1") (pintype "passive"))
      (node (ref "R42") (pin "1") (pinfunction "5_1") (pintype "passive"))
      (node (ref "R48") (pin "1") (pinfunction "5_1") (pintype "passive"))
      (node (ref "R60") (pin "1") (pinfunction "5_1") (pintype "passive"))
      (node (ref "R84") (pin "1") (pinfunction "5_1") (pintype "passive"))
      (node (ref "TB27") (pin "2") (pinfunction "2_2") (pintype "passive"))
      (node (ref "U2") (pin "2") (pinfunction "K_2") (pintype "passive"))
      (node (ref "U2") (pin "3") (pinfunction "E_3") (pintype "passive"))
      (node (ref "U28") (pin "8") (pinfunction "GND_8") (pintype "passive"))
      (node (ref "U3") (pin "2") (pinfunction "K_2") (pintype "passive"))
      (node (ref "U3") (pin "3") (pinfunction "E_3") (pintype "passive"))
      (node (ref "U30") (pin "2") (pinfunction "K_2") (pintype "passive"))
      (node (ref "U31") (pin "GND_L") (pinfunction "GND_L_GND_L") (pintype "passive"))
      (node (ref "U4") (pin "2") (pinfunction "K_2") (pintype "passive"))
      (node (ref "U4") (pin "3") (pinfunction "E_3") (pintype "passive"))
      (node (ref "U5") (pin "2") (pinfunction "K_2") (pintype "passive"))
      (node (ref "U5") (pin "3") (pinfunction "E_3") (pintype "passive"))
      (node (ref "U6") (pin "2") (pinfunction "K_2") (pintype "passive"))
      (node (ref "U6") (pin "3") (pinfunction "E_3") (pintype "passive"))
      (node (ref "U8") (pin "2") (pinfunction "K_2") (pintype "passive"))
      (node (ref "U8") (pin "3") (pinfunction "E_3") (pintype "passive"))
    )
    (net (code "23") (name "Net-(C1-PadA)") (class "Default")
      (node (ref "C1") (pin "A") (pinfunction "A_A") (pintype "passive"))
      (node (ref "D1") (pin "K") (pintype "passive"))
      (node (ref "F2") (pin "2") (pintype "passive"))
      (node (ref "TB10") (pin "2") (pinfunction "2_2") (pintype "passive"))
    )
    (net (code "24") (name "Net-(C16-PadA)") (class "Default")
      (node (ref "C16") (pin "A") (pinfunction "A_A") (pintype "passive"))
      (node (ref "D3") (pin "K") (pintype "passive"))
      (node (ref "F6") (pin "1") (pintype "passive"))
      (node (ref "TB32") (pin "1") (pinfunction "1_1") (pintype "passive"))
    )
    (net (code "25") (name "Net-(C18-PadA)") (class "Default")
      (node (ref "C18") (pin "A") (pinfunction "A_A") (pintype "passive"))
      (node (ref "D4") (pin "K") (pintype "passive"))
      (node (ref "F1") (pin "2") (pintype "passive"))
      (node (ref "TB12") (pin "2") (pinfunction "2_2") (pintype "passive"))
    )
    (net (code "26") (name "Net-(C19-PadA)") (class "Default")
      (node (ref "C19") (pin "A") (pinfunction "A_A") (pintype "passive"))
      (node (ref "D2") (pin "K") (pintype "passive"))
      (node (ref "F3") (pin "2") (pintype "passive"))
      (node (ref "TB11") (pin "2") (pinfunction "2_2") (pintype "passive"))
    )
    (net (code "27") (name "Net-(C21-PadA)") (class "Default")
      (node (ref "C21") (pin "A") (pinfunction "A_A") (pintype "passive"))
      (node (ref "D5") (pin "K") (pintype "passive"))
      (node (ref "F4") (pin "2") (pintype "passive"))
      (node (ref "TB14") (pin "2") (pinfunction "2_2") (pintype "passive"))
    )
    (net (code "28") (name "Net-(C22-PadA)") (class "Default")
      (node (ref "C22") (pin "A") (pinfunction "A_A") (pintype "passive"))
      (node (ref "D7") (pin "K") (pintype "passive"))
      (node (ref "F5") (pin "2") (pintype "passive"))
      (node (ref "TB16") (pin "2") (pinfunction "2_2") (pintype "passive"))
    )
    (net (code "29") (name "Net-(K1-NO)") (class "Default")
      (node (ref "K1") (pin "3") (pinfunction "NO_3") (pintype "passive"))
      (node (ref "TB27") (pin "1") (pinfunction "1_1") (pintype "passive"))
    )
    (net (code "30") (name "Net-(K1-T2)") (class "Default")
      (node (ref "D9") (pin "A") (pinfunction "A_A") (pintype "passive"))
      (node (ref "K1") (pin "5") (pinfunction "T2_5") (pintype "passive"))
      (node (ref "Q12") (pin "3") (pinfunction "C_3") (pintype "passive"))
    )
    (net (code "31") (name "Net-(Q1-B)") (class "Default")
      (node (ref "Q1") (pin "2") (pinfunction "B_2") (pintype "passive"))
      (node (ref "R21") (pin "2") (pinfunction "6_2") (pintype "passive"))
      (node (ref "R64") (pin "1") (pinfunction "5_1") (pintype "passive"))
    )
    (net (code "32") (name "Net-(Q1-C)") (class "Default")
      (node (ref "Q1") (pin "3") (pinfunction "C_3") (pintype "passive"))
      (node (ref "R23") (pin "1") (pinfunction "5_1") (pintype "passive"))
    )
    (net (code "33") (name "Net-(Q2-D)") (class "Default")
      (node (ref "D1") (pin "A") (pintype "passive"))
      (node (ref "Q2") (pin "2") (pinfunction "D_2") (pintype "passive"))
      (node (ref "TB10") (pin "1") (pinfunction "1_1") (pintype "passive"))
    )
    (net (code "34") (name "Net-(Q2-G)") (class "Default")
      (node (ref "Q2") (pin "1") (pinfunction "G_1") (pintype "passive"))
      (node (ref "R23") (pin "2") (pinfunction "6_2") (pintype "passive"))
      (node (ref "R24") (pin "2") (pinfunction "6_2") (pintype "passive"))
    )
    (net (code "35") (name "Net-(Q3-B)") (class "Default")
      (node (ref "Q3") (pin "2") (pinfunction "B_2") (pintype "passive"))
      (node (ref "R27") (pin "2") (pinfunction "6_2") (pintype "passive"))
      (node (ref "R65") (pin "1") (pinfunction "5_1") (pintype "passive"))
    )
    (net (code "36") (name "Net-(Q3-C)") (class "Default")
      (node (ref "Q3") (pin "3") (pinfunction "C_3") (pintype "passive"))
      (node (ref "R29") (pin "1") (pinfunction "5_1") (pintype "passive"))
    )
    (net (code "37") (name "Net-(Q4-D)") (class "Default")
      (node (ref "D2") (pin "A") (pintype "passive"))
      (node (ref "Q4") (pin "2") (pinfunction "D_2") (pintype "passive"))
      (node (ref "TB11") (pin "1") (pinfunction "1_1") (pintype "passive"))
    )
    (net (code "38") (name "Net-(Q4-G)") (class "Default")
      (node (ref "Q4") (pin "1") (pinfunction "G_1") (pintype "passive"))
      (node (ref "R29") (pin "2") (pinfunction "6_2") (pintype "passive"))
      (node (ref "R30") (pin "2") (pinfunction "6_2") (pintype "passive"))
    )
    (net (code "39") (name "Net-(Q5-B)") (class "Default")
      (node (ref "Q5") (pin "2") (pinfunction "B_2") (pintype "passive"))
      (node (ref "R33") (pin "2") (pinfunction "6_2") (pintype "passive"))
      (node (ref "R67") (pin "1") (pinfunction "5_1") (pintype "passive"))
    )
    (net (code "40") (name "Net-(Q5-C)") (class "Default")
      (node (ref "Q5") (pin "3") (pinfunction "C_3") (pintype "passive"))
      (node (ref "R35") (pin "1") (pinfunction "5_1") (pintype "passive"))
    )
    (net (code "41") (name "Net-(Q6-D)") (class "Default")
      (node (ref "D3") (pin "A") (pintype "passive"))
      (node (ref "Q6") (pin "2") (pinfunction "D_2") (pintype "passive"))
      (node (ref "TB32") (pin "2") (pinfunction "2_2") (pintype "passive"))
    )
    (net (code "42") (name "Net-(Q6-G)") (class "Default")
      (node (ref "Q6") (pin "1") (pinfunction "G_1") (pintype "passive"))
      (node (ref "R35") (pin "2") (pinfunction "6_2") (pintype "passive"))
      (node (ref "R36") (pin "2") (pinfunction "6_2") (pintype "passive"))
    )
    (net (code "43") (name "Net-(Q7-B)") (class "Default")
      (node (ref "Q7") (pin "2") (pinfunction "B_2") (pintype "passive"))
      (node (ref "R39") (pin "2") (pinfunction "6_2") (pintype "passive"))
      (node (ref "R63") (pin "1") (pinfunction "5_1") (pintype "passive"))
    )
    (net (code "44") (name "Net-(Q7-C)") (class "Default")
      (node (ref "Q7") (pin "3") (pinfunction "C_3") (pintype "passive"))
      (node (ref "R41") (pin "1") (pinfunction "5_1") (pintype "passive"))
    )
    (net (code "45") (name "Net-(Q8-D)") (class "Default")
      (node (ref "D4") (pin "A") (pintype "passive"))
      (node (ref "Q8") (pin "2") (pinfunction "D_2") (pintype "passive"))
      (node (ref "TB12") (pin "1") (pinfunction "1_1") (pintype "passive"))
    )
    (net (code "46") (name "Net-(Q8-G)") (class "Default")
      (node (ref "Q8") (pin "1") (pinfunction "G_1") (pintype "passive"))
      (node (ref "R41") (pin "2") (pinfunction "6_2") (pintype "passive"))
      (node (ref "R42") (pin "2") (pinfunction "6_2") (pintype "passive"))
    )
    (net (code "47") (name "Net-(Q9-B)") (class "Default")
      (node (ref "Q9") (pin "2") (pinfunction "B_2") (pintype "passive"))
      (node (ref "R45") (pin "2") (pinfunction "6_2") (pintype "passive"))
      (node (ref "R66") (pin "1") (pinfunction "5_1") (pintype "passive"))
    )
    (net (code "48") (name "Net-(Q9-C)") (class "Default")
      (node (ref "Q9") (pin "3") (pinfunction "C_3") (pintype "passive"))
      (node (ref "R47") (pin "1") (pinfunction "5_1") (pintype "passive"))
    )
    (net (code "49") (name "Net-(Q10-D)") (class "Default")
      (node (ref "D5") (pin "A") (pintype "passive"))
      (node (ref "Q10") (pin "2") (pinfunction "D_2") (pintype "passive"))
      (node (ref "TB14") (pin "1") (pinfunction "1_1") (pintype "passive"))
    )
    (net (code "50") (name "Net-(Q10-G)") (class "Default")
      (node (ref "Q10") (pin "1") (pinfunction "G_1") (pintype "passive"))
      (node (ref "R47") (pin "2") (pinfunction "6_2") (pintype "passive"))
      (node (ref "R48") (pin "2") (pinfunction "6_2") (pintype "passive"))
    )
    (net (code "51") (name "Net-(Q12-B)") (class "Default")
      (node (ref "Q12") (pin "2") (pinfunction "B_2") (pintype "passive"))
      (node (ref "R4") (pin "2") (pinfunction "6_2") (pintype "passive"))
    )
    (net (code "52") (name "Net-(Q13-B)") (class "Default")
      (node (ref "Q13") (pin "2") (pinfunction "B_2") (pintype "passive"))
      (node (ref "R56") (pin "2") (pinfunction "6_2") (pintype "passive"))
      (node (ref "R68") (pin "1") (pinfunction "5_1") (pintype "passive"))
    )
    (net (code "53") (name "Net-(Q13-C)") (class "Default")
      (node (ref "Q13") (pin "3") (pinfunction "C_3") (pintype "passive"))
      (node (ref "R59") (pin "1") (pinfunction "5_1") (pintype "passive"))
    )
    (net (code "54") (name "Net-(Q14-D)") (class "Default")
      (node (ref "D7") (pin "A") (pintype "passive"))
      (node (ref "Q14") (pin "2") (pinfunction "D_2") (pintype "passive"))
      (node (ref "TB16") (pin "1") (pinfunction "1_1") (pintype "passive"))
    )
    (net (code "55") (name "Net-(Q14-G)") (class "Default")
      (node (ref "Q14") (pin "1") (pinfunction "G_1") (pintype "passive"))
      (node (ref "R59") (pin "2") (pinfunction "6_2") (pintype "passive"))
      (node (ref "R60") (pin "2") (pinfunction "6_2") (pintype "passive"))
    )
    (net (code "56") (name "Net-(R3-6)") (class "Default")
      (node (ref "R3") (pin "2") (pinfunction "6_2") (pintype "passive"))
      (node (ref "U30") (pin "1") (pinfunction "A_1") (pintype "passive"))
    )
    (net (code "57") (name "Net-(R4-5)") (class "Default")
      (node (ref "R4") (pin "1") (pinfunction "5_1") (pintype "passive"))
      (node (ref "R84") (pin "2") (pinfunction "6_2") (pintype "passive"))
      (node (ref "U30") (pin "3") (pinfunction "E_3") (pintype "passive"))
    )
    (net (code "58") (name "Net-(R19-5)") (class "Default")
      (node (ref "R19") (pin "1") (pinfunction "5_1") (pintype "passive"))
      (node (ref "R21") (pin "1") (pinfunction "5_1") (pintype "passive"))
      (node (ref "U2") (pin "4") (pinfunction "C_4") (pintype "passive"))
    )
    (net (code "59") (name "Net-(R20-6)") (class "Default")
      (node (ref "R20") (pin "2") (pinfunction "6_2") (pintype "passive"))
      (node (ref "U2") (pin "1") (pinfunction "A_1") (pintype "passive"))
    )
    (net (code "60") (name "Net-(R25-5)") (class "Default")
      (node (ref "R25") (pin "1") (pinfunction "5_1") (pintype "passive"))
      (node (ref "R27") (pin "1") (pinfunction "5_1") (pintype "passive"))
      (node (ref "U3") (pin "4") (pinfunction "C_4") (pintype "passive"))
    )
    (net (code "61") (name "Net-(R26-6)") (class "Default")
      (node (ref "R26") (pin "2") (pinfunction "6_2") (pintype "passive"))
      (node (ref "U3") (pin "1") (pinfunction "A_1") (pintype "passive"))
    )
    (net (code "62") (name "Net-(R31-5)") (class "Default")
      (node (ref "R31") (pin "1") (pinfunction "5_1") (pintype "passive"))
      (node (ref "R33") (pin "1") (pinfunction "5_1") (pintype "passive"))
      (node (ref "U4") (pin "4") (pinfunction "C_4") (pintype "passive"))
    )
    (net (code "63") (name "Net-(R32-6)") (class "Default")
      (node (ref "R32") (pin "2") (pinfunction "6_2") (pintype "passive"))
      (node (ref "U4") (pin "1") (pinfunction "A_1") (pintype "passive"))
    )
    (net (code "64") (name "Net-(R37-5)") (class "Default")
      (node (ref "R37") (pin "1") (pinfunction "5_1") (pintype "passive"))
      (node (ref "R39") (pin "1") (pinfunction "5_1") (pintype "passive"))
      (node (ref "U5") (pin "4") (pinfunction "C_4") (pintype "passive"))
    )
    (net (code "65") (name "Net-(R38-6)") (class "Default")
      (node (ref "R38") (pin "2") (pinfunction "6_2") (pintype "passive"))
      (node (ref "U5") (pin "1") (pinfunction "A_1") (pintype "passive"))
    )
    (net (code "66") (name "Net-(R43-5)") (class "Default")
      (node (ref "R43") (pin "1") (pinfunction "5_1") (pintype "passive"))
      (node (ref "R45") (pin "1") (pinfunction "5_1") (pintype "passive"))
      (node (ref "U6") (pin "4") (pinfunction "C_4") (pintype "passive"))
    )
    (net (code "67") (name "Net-(R44-6)") (class "Default")
      (node (ref "R44") (pin "2") (pinfunction "6_2") (pintype "passive"))
      (node (ref "U6") (pin "1") (pinfunction "A_1") (pintype "passive"))
    )
    (net (code "68") (name "Net-(R53-5)") (class "Default")
      (node (ref "R53") (pin "1") (pinfunction "5_1") (pintype "passive"))
      (node (ref "R56") (pin "1") (pinfunction "5_1") (pintype "passive"))
      (node (ref "U8") (pin "4") (pinfunction "C_4") (pintype "passive"))
    )
    (net (code "69") (name "Net-(R55-6)") (class "Default")
      (node (ref "R55") (pin "2") (pinfunction "6_2") (pintype "passive"))
      (node (ref "U8") (pin "1") (pinfunction "A_1") (pintype "passive"))
    )
    (net (code "70") (name "Net-(TB34-Pad1)") (class "Default")
      (node (ref "TB34") (pin "1") (pinfunction "1_1") (pintype "passive"))
      (node (ref "U31") (pin "GND_MOT") (pinfunction "GND_MOT_GND_MOT") (pintype "passive"))
    )
    (net (code "71") (name "Net-(TB35-Pad1)") (class "Default")
      (node (ref "TB35") (pin "1") (pinfunction "1_1") (pintype "passive"))
      (node (ref "U31") (pin "A2") (pinfunction "A2_A2") (pintype "passive"))
    )
    (net (code "72") (name "Net-(TB35-Pad2)") (class "Default")
      (node (ref "TB35") (pin "2") (pinfunction "2_2") (pintype "passive"))
      (node (ref "U31") (pin "A1") (pinfunction "A1_A1") (pintype "passive"))
    )
    (net (code "73") (name "Net-(TB38-Pad1)") (class "Default")
      (node (ref "TB38") (pin "1") (pinfunction "1_1") (pintype "passive"))
      (node (ref "U31") (pin "B1") (pinfunction "B1_B1") (pintype "passive"))
    )
    (net (code "74") (name "Net-(TB38-Pad2)") (class "Default")
      (node (ref "TB38") (pin "2") (pinfunction "2_2") (pintype "passive"))
      (node (ref "U31") (pin "B2") (pinfunction "B2_B2") (pintype "passive"))
    )
    (net (code "75") (name "unconnected-(K1-NC-Pad2)") (class "Default")
      (node (ref "K1") (pin "2") (pinfunction "NC_2") (pintype "passive"))
    )
    (net (code "76") (name "unconnected-(U28-Q0-Pad15)") (class "Default")
      (node (ref "U28") (pin "15") (pinfunction "Q0_15") (pintype "output+no_connect"))
    )
    (net (code "77") (name "unconnected-(U28-Q7-Pad7)") (class "Default")
      (node (ref "U28") (pin "7") (pinfunction "Q7_7") (pintype "output+no_connect"))
    )
    (net (code "78") (name "unconnected-(U31-PadM0)") (class "Default")
      (node (ref "U31") (pin "M0") (pinfunction "M0_M0") (pintype "passive+no_connect"))
    )
    (net (code "79") (name "unconnected-(U31-PadM1)") (class "Default")
      (node (ref "U31") (pin "M1") (pinfunction "M1_M1") (pintype "passive+no_connect"))
    )
    (net (code "80") (name "unconnected-(U31-PadM2)") (class "Default")
      (node (ref "U31") (pin "M2") (pinfunction "M2_M2") (pintype "passive+no_connect"))
    )
  )
)
